# Power.net
KiCad netlist of a schematic drawn in Altium Designer
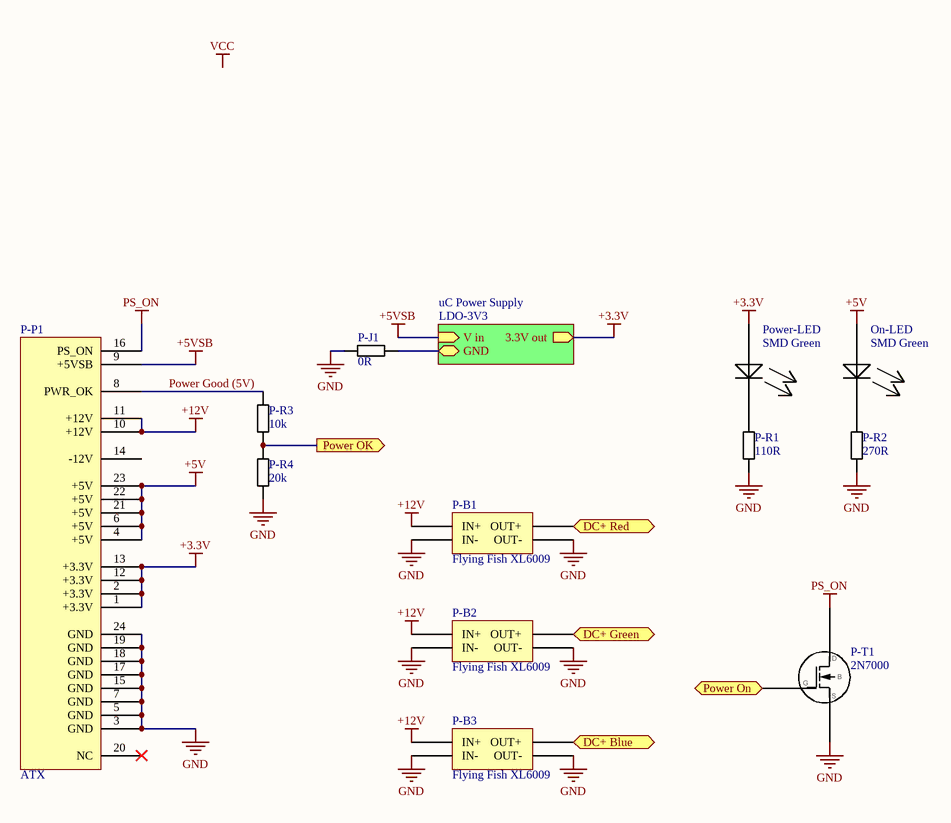
[diagram p0: Power.SchDoc]

(export (version "E")
  (design (tool "Eeschema 10.0.6"))
  (components
    (comp (ref "On-LED") (value "SMD Green") (footprint "LED 0603") (libsource (lib "LEDs") (part "LED")))
    (comp (ref "P-B1")
      (value "Flying Fish XL6009")
      (footprint "Flying Fish XL6009 small")
      (libsource (lib "Modules") (part "Flying Fish XL6009"))
    )
    (comp (ref "P-B2")
      (value "Flying Fish XL6009")
      (footprint "Flying Fish XL6009 small")
      (libsource (lib "Modules") (part "Flying Fish XL6009"))
    )
    (comp (ref "P-B3")
      (value "Flying Fish XL6009")
      (footprint "Flying Fish XL6009 small")
      (libsource (lib "Modules") (part "Flying Fish XL6009"))
    )
    (comp (ref "P-J1") (value "0R") (footprint "R 0805 / 2012 wide") (libsource (lib "") (part "Resistor_1")))
    (comp (ref "P-P1") (value "ATX") (footprint "ATX") (libsource (lib "Connectors") (part "ATX sorted")))
    (comp (ref "P-R1")
      (value "110R")
      (footprint "R 0805 / 2012")
      (libsource (lib "Standard") (part "Resistor"))
    )
    (comp (ref "P-R2")
      (value "270R")
      (footprint "R 0805 / 2012")
      (libsource (lib "Standard") (part "Resistor"))
    )
    (comp (ref "P-R3")
      (value "10k")
      (footprint "R 0805 / 2012")
      (libsource (lib "Standard") (part "Resistor"))
    )
    (comp (ref "P-R4")
      (value "20k")
      (footprint "R 0805 / 2012")
      (libsource (lib "Standard") (part "Resistor"))
    )
    (comp (ref "P-T1")
      (value "2N7000")
      (footprint "SOT-23-3")
      (description "N-FET")
      (libsource (lib "ICs") (part "2N7000"))
    )
    (comp (ref "Power-LED") (value "SMD Green") (footprint "LED 0603") (libsource (lib "LEDs") (part "LED")))
  )
  (nets
    (net (code "1") (name "+3.3V") (class "Default")
      (node (ref "P-P1") (pin "1") (pinfunction "+3.3V_1") (pintype "passive"))
      (node (ref "P-P1") (pin "12") (pinfunction "+3.3V_12") (pintype "passive"))
      (node (ref "P-P1") (pin "13") (pinfunction "+3.3V_13") (pintype "passive"))
      (node (ref "P-P1") (pin "2") (pinfunction "+3.3V_2") (pintype "passive"))
      (node (ref "Power-LED") (pin "1") (pinfunction "+_1") (pintype "passive"))
    )
    (net (code "2") (name "+5V") (class "Default")
      (node (ref "On-LED") (pin "1") (pinfunction "+_1") (pintype "passive"))
      (node (ref "P-P1") (pin "21") (pinfunction "+5V_21") (pintype "passive"))
      (node (ref "P-P1") (pin "22") (pinfunction "+5V_22") (pintype "passive"))
      (node (ref "P-P1") (pin "23") (pinfunction "+5V_23") (pintype "passive"))
      (node (ref "P-P1") (pin "4") (pinfunction "+5V_4") (pintype "passive"))
      (node (ref "P-P1") (pin "6") (pinfunction "+5V_6") (pintype "passive"))
    )
    (net (code "3") (name "+5VSB") (class "Default")
      (node (ref "P-P1") (pin "9") (pinfunction "+5VSB_9") (pintype "passive"))
    )
    (net (code "4") (name "+12V") (class "Default")
      (node (ref "P-B1") (pin "IN+") (pinfunction "IN+_IN+") (pintype "passive"))
      (node (ref "P-B2") (pin "IN+") (pinfunction "IN+_IN+") (pintype "passive"))
      (node (ref "P-B3") (pin "IN+") (pinfunction "IN+_IN+") (pintype "passive"))
      (node (ref "P-P1") (pin "10") (pinfunction "+12V_10") (pintype "passive"))
      (node (ref "P-P1") (pin "11") (pinfunction "+12V_11") (pintype "passive"))
    )
    (net (code "5") (name "/DC+ Blue") (class "Default")
      (node (ref "P-B3") (pin "OUT+") (pinfunction "OUT+_OUT+") (pintype "passive"))
    )
    (net (code "6") (name "/DC+ Green") (class "Default")
      (node (ref "P-B2") (pin "OUT+") (pinfunction "OUT+_OUT+") (pintype "passive"))
    )
    (net (code "7") (name "/DC+ Red") (class "Default")
      (node (ref "P-B1") (pin "OUT+") (pinfunction "OUT+_OUT+") (pintype "passive"))
    )
    (net (code "8") (name "/GND") (class "Default")
      (node (ref "P-J1") (pin "2") (pinfunction "2_2") (pintype "passive"))
    )
    (net (code "9") (name "/Power Good (5V)") (class "Default")
      (node (ref "P-P1") (pin "8") (pinfunction "PWR_OK_8") (pintype "passive"))
      (node (ref "P-R3") (pin "2") (pinfunction "2_2") (pintype "passive"))
    )
    (net (code "10") (name "/Power OK") (class "Default")
      (node (ref "P-R3") (pin "1") (pinfunction "1_1") (pintype "passive"))
      (node (ref "P-R4") (pin "2") (pinfunction "2_2") (pintype "passive"))
    )
    (net (code "11") (name "/Power On") (class "Default")
      (node (ref "P-T1") (pin "1") (pinfunction "1_1") (pintype "passive"))
    )
    (net (code "12") (name "GND") (class "Default")
      (node (ref "P-B1") (pin "IN-") (pinfunction "IN-_IN-") (pintype "passive"))
      (node (ref "P-B1") (pin "OUT-") (pinfunction "OUT-_OUT-") (pintype "passive"))
      (node (ref "P-B2") (pin "IN-") (pinfunction "IN-_IN-") (pintype "passive"))
      (node (ref "P-B2") (pin "OUT-") (pinfunction "OUT-_OUT-") (pintype "passive"))
      (node (ref "P-B3") (pin "IN-") (pinfunction "IN-_IN-") (pintype "passive"))
      (node (ref "P-B3") (pin "OUT-") (pinfunction "OUT-_OUT-") (pintype "passive"))
      (node (ref "P-J1") (pin "1") (pinfunction "1_1") (pintype "passive"))
      (node (ref "P-P1") (pin "15") (pinfunction "GND_15") (pintype "passive"))
      (node (ref "P-P1") (pin "17") (pinfunction "GND_17") (pintype "passive"))
      (node (ref "P-P1") (pin "18") (pinfunction "GND_18") (pintype "passive"))
      (node (ref "P-P1") (pin "19") (pinfunction "GND_19") (pintype "passive"))
      (node (ref "P-P1") (pin "24") (pinfunction "GND_24") (pintype "passive"))
      (node (ref "P-P1") (pin "3") (pinfunction "GND_3") (pintype "passive"))
      (node (ref "P-P1") (pin "5") (pinfunction "GND_5") (pintype "passive"))
      (node (ref "P-P1") (pin "7") (pinfunction "GND_7") (pintype "passive"))
      (node (ref "P-R1") (pin "1") (pinfunction "1_1") (pintype "passive"))
      (node (ref "P-R2") (pin "1") (pinfunction "1_1") (pintype "passive"))
      (node (ref "P-R4") (pin "1") (pinfunction "1_1") (pintype "passive"))
      (node (ref "P-T1") (pin "2") (pinfunction "2_2") (pintype "passive"))
    )
    (net (code "13") (name "Net-(On-LED--)") (class "Default")
      (node (ref "On-LED") (pin "2") (pinfunction "-_2") (pintype "passive"))
      (node (ref "P-R2") (pin "2") (pinfunction "2_2") (pintype "passive"))
    )
    (net (code "14") (name "Net-(Power-LED--)") (class "Default")
      (node (ref "P-R1") (pin "2") (pinfunction "2_2") (pintype "passive"))
      (node (ref "Power-LED") (pin "2") (pinfunction "-_2") (pintype "passive"))
    )
    (net (code "15") (name "PS_ON") (class "Default")
      (node (ref "P-P1") (pin "16") (pinfunction "PS_ON_16") (pintype "passive"))
      (node (ref "P-T1") (pin "3") (pinfunction "3_3") (pintype "passive"))
    )
    (net (code "17") (name "unconnected-(P-P1--12V-Pad14)") (class "Default")
      (node (ref "P-P1") (pin "14") (pinfunction "-12V_14") (pintype "passive"))
    )
    (net (code "18") (name "unconnected-(P-P1-NC-Pad20)") (class "Default")
      (node (ref "P-P1") (pin "20") (pinfunction "NC_20") (pintype "passive+no_connect"))
    )
  )
)
